# LEDs.net
KiCad netlist of a schematic drawn in Altium Designer
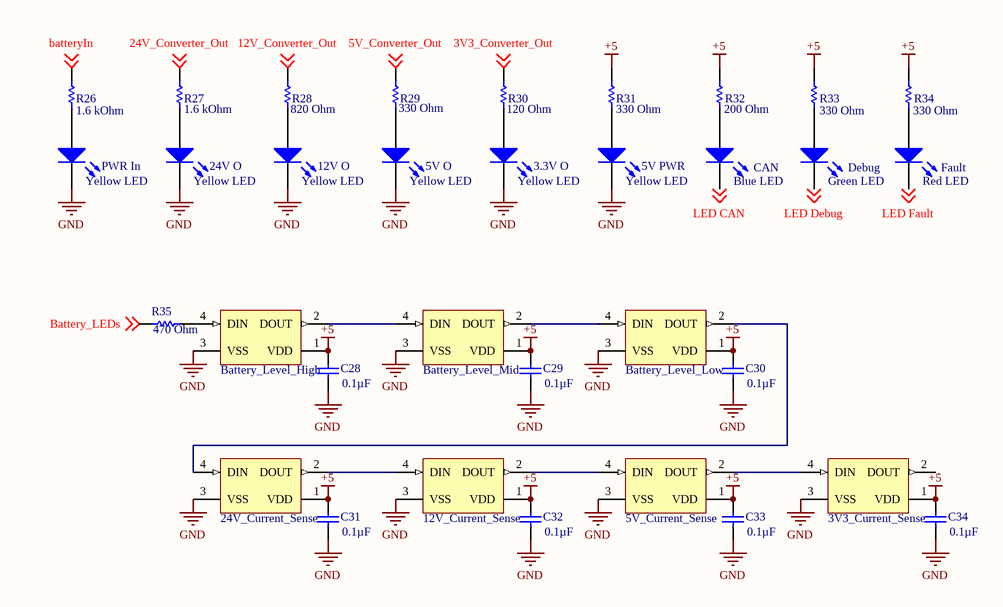
[diagram p0: LEDs.SchDoc]

(export (version "E")
  (design (tool "Eeschema 10.0.6"))
  (components
    (comp (ref "3.3V O")
      (value "Yellow LED")
      (footprint "0805_A")
      (description "Standard 0805 LED")
      (libsource (lib "Husky Robotics Standard Library 2019-2020") (part "LED"))
    )
    (comp (ref "3V3_Current_Sense")
      (value "RBG_LED")
      (footprint "RGB_LED_1")
      (description "LED ADAI-WS2812B-4")
      (fields (field (name "DIGI-KEY_PART_NUMBER") "516-3280-1-ND"))
      (libsource (lib "University of Washington - Husky Robotics Team") (part "RBG_LED"))
    )
    (comp (ref "5V O")
      (value "Yellow LED")
      (footprint "0805_A")
      (description "Standard 0805 LED")
      (libsource (lib "Husky Robotics Standard Library 2019-2020") (part "LED"))
    )
    (comp (ref "5V PWR")
      (value "Yellow LED")
      (footprint "0805_A")
      (description "Standard 0805 LED")
      (libsource (lib "Husky Robotics Standard Library 2019-2020") (part "LED"))
    )
    (comp (ref "5V_Current_Sense")
      (value "RBG_LED")
      (footprint "RGB_LED_1")
      (description "LED ADAI-WS2812B-4")
      (fields (field (name "DIGI-KEY_PART_NUMBER") "516-3280-1-ND"))
      (libsource (lib "University of Washington - Husky Robotics Team") (part "RBG_LED"))
    )
    (comp (ref "12V O")
      (value "Yellow LED")
      (footprint "0805_A")
      (description "Standard 0805 LED")
      (libsource (lib "Husky Robotics Standard Library 2019-2020") (part "LED"))
    )
    (comp (ref "12V_Current_Sense")
      (value "RBG_LED")
      (footprint "RGB_LED_1")
      (description "LED ADAI-WS2812B-4")
      (fields (field (name "DIGI-KEY_PART_NUMBER") "516-3280-1-ND"))
      (libsource (lib "University of Washington - Husky Robotics Team") (part "RBG_LED"))
    )
    (comp (ref "24V O")
      (value "Yellow LED")
      (footprint "0805_A")
      (description "Standard 0805 LED")
      (libsource (lib "Husky Robotics Standard Library 2019-2020") (part "LED"))
    )
    (comp (ref "24V_Current_Sense")
      (value "RBG_LED")
      (footprint "RGB_LED_1")
      (description "LED ADAI-WS2812B-4")
      (fields (field (name "DIGI-KEY_PART_NUMBER") "516-3280-1-ND"))
      (libsource (lib "University of Washington - Husky Robotics Team") (part "RBG_LED"))
    )
    (comp (ref "Battery_Level_High")
      (value "RBG_LED")
      (footprint "RGB_LED_1")
      (description "LED ADAI-WS2812B-4")
      (fields (field (name "DIGI-KEY_PART_NUMBER") "516-3280-1-ND"))
      (libsource (lib "University of Washington - Husky Robotics Team") (part "RBG_LED"))
    )
    (comp (ref "Battery_Level_Low")
      (value "RBG_LED")
      (footprint "RGB_LED_1")
      (description "LED ADAI-WS2812B-4")
      (fields (field (name "DIGI-KEY_PART_NUMBER") "516-3280-1-ND"))
      (libsource (lib "University of Washington - Husky Robotics Team") (part "RBG_LED"))
    )
    (comp (ref "Battery_Level_Mid")
      (value "RBG_LED")
      (footprint "RGB_LED_1")
      (description "LED ADAI-WS2812B-4")
      (fields (field (name "DIGI-KEY_PART_NUMBER") "516-3280-1-ND"))
      (libsource (lib "University of Washington - Husky Robotics Team") (part "RBG_LED"))
    )
    (comp (ref "C28")
      (value "0.1µF")
      (footprint "Cap 0805")
      (description "Standard Capacitor")
      (fields (field (name "DIGI-KEY_PART_NUMBER") "399-1177-1-ND") (field (name "Comment") "0805 Capacitor"))
      (libsource (lib "University of Washington - Husky Robotics Team") (part "0805 Capacitor"))
    )
    (comp (ref "C29")
      (value "0.1µF")
      (footprint "Cap 0805")
      (description "Standard Capacitor")
      (fields (field (name "DIGI-KEY_PART_NUMBER") "399-1177-1-ND") (field (name "Comment") "0805 Capacitor"))
      (libsource (lib "University of Washington - Husky Robotics Team") (part "0805 Capacitor"))
    )
    (comp (ref "C30")
      (value "0.1µF")
      (footprint "Cap 0805")
      (description "Standard Capacitor")
      (fields (field (name "DIGI-KEY_PART_NUMBER") "399-1177-1-ND") (field (name "Comment") "0805 Capacitor"))
      (libsource (lib "University of Washington - Husky Robotics Team") (part "0805 Capacitor"))
    )
    (comp (ref "C31")
      (value "0.1µF")
      (footprint "Cap 0805")
      (description "Standard Capacitor")
      (fields (field (name "DIGI-KEY_PART_NUMBER") "399-1177-1-ND") (field (name "Comment") "0805 Capacitor"))
      (libsource (lib "University of Washington - Husky Robotics Team") (part "0805 Capacitor"))
    )
    (comp (ref "C32")
      (value "0.1µF")
      (footprint "Cap 0805")
      (description "Standard Capacitor")
      (fields (field (name "DIGI-KEY_PART_NUMBER") "399-1177-1-ND") (field (name "Comment") "0805 Capacitor"))
      (libsource (lib "University of Washington - Husky Robotics Team") (part "0805 Capacitor"))
    )
    (comp (ref "C33")
      (value "0.1µF")
      (footprint "Cap 0805")
      (description "Standard Capacitor")
      (fields (field (name "DIGI-KEY_PART_NUMBER") "399-1177-1-ND") (field (name "Comment") "0805 Capacitor"))
      (libsource (lib "University of Washington - Husky Robotics Team") (part "0805 Capacitor"))
    )
    (comp (ref "C34")
      (value "0.1µF")
      (footprint "Cap 0805")
      (description "Standard Capacitor")
      (fields (field (name "DIGI-KEY_PART_NUMBER") "399-1177-1-ND") (field (name "Comment") "0805 Capacitor"))
      (libsource (lib "University of Washington - Husky Robotics Team") (part "0805 Capacitor"))
    )
    (comp (ref "CAN")
      (value "Blue LED")
      (footprint "0805_A")
      (description "Standard 0805 LED")
      (libsource (lib "Husky Robotics Standard Library 2019-2020") (part "LED"))
    )
    (comp (ref "Debug")
      (value "Green LED")
      (footprint "0805_A")
      (description "Standard 0805 LED")
      (libsource (lib "Husky Robotics Standard Library 2019-2020") (part "LED"))
    )
    (comp (ref "Fault")
      (value "Red LED")
      (footprint "0805_A")
      (description "Standard 0805 LED")
      (fields (field (name "MANUFACTURER") "Wuerth Elektronik") (field (name "PARTNUMBER") "150080SS75000"))
      (libsource (lib "Husky Robotics Standard Library 2019-2020") (part "LED"))
    )
    (comp (ref "PWR In")
      (value "Yellow LED")
      (footprint "0805_A")
      (description "Standard 0805 LED")
      (libsource (lib "Husky Robotics Standard Library 2019-2020") (part "LED"))
    )
    (comp (ref "R26")
      (value "1.6 kOhm")
      (footprint "RESC0805(2012)_N")
      (description "Generic 0805 Resistor")
      (fields (field (name "Comment") "Resistor 0805"))
      (libsource (lib "Husky Robotics Standard Library 2019-2020") (part "Resistor 0805"))
    )
    (comp (ref "R27")
      (value "1.6 kOhm")
      (footprint "RESC0805(2012)_N")
      (description "Generic 0805 Resistor")
      (fields (field (name "Comment") "Resistor 0805"))
      (libsource (lib "Husky Robotics Standard Library 2019-2020") (part "Resistor 0805"))
    )
    (comp (ref "R28")
      (value "820 Ohm")
      (footprint "RESC0805(2012)_N")
      (description "Generic 0805 Resistor")
      (fields (field (name "TOLERANCE") "5 %") (field (name "POWER") "0.125 W"))
      (libsource (lib "Husky Robotics Standard Library 2019-2020") (part "Resistor 0805"))
    )
    (comp (ref "R29")
      (value "330 Ohm")
      (footprint "RESC0805(2012)_N")
      (description "Generic 0805 Resistor")
      (fields (field (name "Comment") "Resistor 0805"))
      (libsource (lib "Husky Robotics Standard Library 2019-2020") (part "Resistor 0805"))
    )
    (comp (ref "R30")
      (value "120 Ohm")
      (footprint "RESC0805(2012)_N")
      (description "Generic 0805 Resistor")
      (fields (field (name "TOLERANCE") "5 %") (field (name "POWER") "0.125 W"))
      (libsource (lib "Husky Robotics Standard Library 2019-2020") (part "Resistor 0805"))
    )
    (comp (ref "R31")
      (value "330 Ohm")
      (footprint "RESC0805(2012)_N")
      (description "Generic 0805 Resistor")
      (fields (field (name "Comment") "Resistor 0805"))
      (libsource (lib "Husky Robotics Standard Library 2019-2020") (part "Resistor 0805"))
    )
    (comp (ref "R32")
      (value "200 Ohm")
      (footprint "RESC0805(2012)_N")
      (description "Generic 0805 Resistor")
      (fields (field (name "Comment") "Resistor 0805"))
      (libsource (lib "Husky Robotics Standard Library 2019-2020") (part "Resistor 0805"))
    )
    (comp (ref "R33")
      (value "330 Ohm")
      (footprint "RESC0805(2012)_N")
      (description "Generic 0805 Resistor")
      (fields (field (name "Comment") "Resistor 0805"))
      (libsource (lib "Husky Robotics Standard Library 2019-2020") (part "Resistor 0805"))
    )
    (comp (ref "R34")
      (value "330 Ohm")
      (footprint "RESC0805(2012)_N")
      (description "Generic 0805 Resistor")
      (fields (field (name "Comment") "Resistor 0805"))
      (libsource (lib "Husky Robotics Standard Library 2019-2020") (part "Resistor 0805"))
    )
    (comp (ref "R35")
      (value "470 Ohm")
      (footprint "RESC0805(2012)_N")
      (description "Generic 0805 Resistor")
      (fields (field (name "Comment") "Resistor 0805"))
      (libsource (lib "University of Washington - Husky Robotics Team") (part "Resistor 0805"))
    )
  )
  (nets
    (net (code "1") (name "+5") (class "Default")
      (node (ref "12V_Current_Sense") (pin "1") (pinfunction "VDD_1") (pintype "power_in"))
      (node (ref "24V_Current_Sense") (pin "1") (pinfunction "VDD_1") (pintype "power_in"))
      (node (ref "3V3_Current_Sense") (pin "1") (pinfunction "VDD_1") (pintype "power_in"))
      (node (ref "5V_Current_Sense") (pin "1") (pinfunction "VDD_1") (pintype "power_in"))
      (node (ref "Battery_Level_High") (pin "1") (pinfunction "VDD_1") (pintype "power_in"))
      (node (ref "Battery_Level_Low") (pin "1") (pinfunction "VDD_1") (pintype "power_in"))
      (node (ref "Battery_Level_Mid") (pin "1") (pinfunction "VDD_1") (pintype "power_in"))
      (node (ref "C28") (pin "1") (pinfunction "1_1") (pintype "passive"))
      (node (ref "C29") (pin "1") (pinfunction "1_1") (pintype "passive"))
      (node (ref "C30") (pin "1") (pinfunction "1_1") (pintype "passive"))
      (node (ref "C31") (pin "1") (pinfunction "1_1") (pintype "passive"))
      (node (ref "C32") (pin "1") (pinfunction "1_1") (pintype "passive"))
      (node (ref "C33") (pin "1") (pinfunction "1_1") (pintype "passive"))
      (node (ref "C34") (pin "1") (pinfunction "1_1") (pintype "passive"))
      (node (ref "R31") (pin "1") (pinfunction "1_1") (pintype "passive"))
      (node (ref "R32") (pin "2") (pinfunction "2_2") (pintype "passive"))
      (node (ref "R33") (pin "2") (pinfunction "2_2") (pintype "passive"))
      (node (ref "R34") (pin "2") (pinfunction "2_2") (pintype "passive"))
    )
    (net (code "2") (name "3V3_Converter_Out") (class "Default")
      (node (ref "R30") (pin "1") (pinfunction "1_1") (pintype "passive"))
    )
    (net (code "3") (name "5V_Converter_Out") (class "Default")
      (node (ref "R29") (pin "1") (pinfunction "1_1") (pintype "passive"))
    )
    (net (code "4") (name "12V_Converter_Out") (class "Default")
      (node (ref "R28") (pin "2") (pinfunction "2_2") (pintype "passive"))
    )
    (net (code "5") (name "24V_Converter_Out") (class "Default")
      (node (ref "R27") (pin "1") (pinfunction "1_1") (pintype "passive"))
    )
    (net (code "6") (name "Battery_LEDs") (class "Default")
      (node (ref "R35") (pin "1") (pinfunction "1_1") (pintype "passive"))
    )
    (net (code "7") (name "GND") (class "Default")
      (node (ref "12V O") (pin "1") (pinfunction "K_1") (pintype "passive"))
      (node (ref "12V_Current_Sense") (pin "3") (pinfunction "VSS_3") (pintype "power_in"))
      (node (ref "24V O") (pin "1") (pinfunction "K_1") (pintype "passive"))
      (node (ref "24V_Current_Sense") (pin "3") (pinfunction "VSS_3") (pintype "power_in"))
      (node (ref "3.3V O") (pin "1") (pinfunction "K_1") (pintype "passive"))
      (node (ref "3V3_Current_Sense") (pin "3") (pinfunction "VSS_3") (pintype "power_in"))
      (node (ref "5V O") (pin "1") (pinfunction "K_1") (pintype "passive"))
      (node (ref "5V PWR") (pin "1") (pinfunction "K_1") (pintype "passive"))
      (node (ref "5V_Current_Sense") (pin "3") (pinfunction "VSS_3") (pintype "power_in"))
      (node (ref "Battery_Level_High") (pin "3") (pinfunction "VSS_3") (pintype "power_in"))
      (node (ref "Battery_Level_Low") (pin "3") (pinfunction "VSS_3") (pintype "power_in"))
      (node (ref "Battery_Level_Mid") (pin "3") (pinfunction "VSS_3") (pintype "power_in"))
      (node (ref "C28") (pin "2") (pinfunction "2_2") (pintype "passive"))
      (node (ref "C29") (pin "2") (pinfunction "2_2") (pintype "passive"))
      (node (ref "C30") (pin "2") (pinfunction "2_2") (pintype "passive"))
      (node (ref "C31") (pin "2") (pinfunction "2_2") (pintype "passive"))
      (node (ref "C32") (pin "2") (pinfunction "2_2") (pintype "passive"))
      (node (ref "C33") (pin "2") (pinfunction "2_2") (pintype "passive"))
      (node (ref "C34") (pin "2") (pinfunction "2_2") (pintype "passive"))
      (node (ref "PWR In") (pin "1") (pinfunction "K_1") (pintype "passive"))
    )
    (net (code "8") (name "LED CAN") (class "Default")
      (node (ref "CAN") (pin "1") (pinfunction "K_1") (pintype "passive"))
    )
    (net (code "9") (name "LED Debug") (class "Default")
      (node (ref "Debug") (pin "1") (pinfunction "K_1") (pintype "passive"))
    )
    (net (code "10") (name "LED Fault") (class "Default")
      (node (ref "Fault") (pin "1") (pinfunction "K_1") (pintype "passive"))
    )
    (net (code "11") (name "Net-(3.3V O-A)") (class "Default")
      (node (ref "3.3V O") (pin "2") (pinfunction "A_2") (pintype "passive"))
      (node (ref "R30") (pin "2") (pinfunction "2_2") (pintype "passive"))
    )
    (net (code "12") (name "Net-(3V3_Current_Sense-DIN)") (class "Default")
      (node (ref "3V3_Current_Sense") (pin "4") (pinfunction "DIN_4") (pintype "input"))
      (node (ref "5V_Current_Sense") (pin "2") (pinfunction "DOUT_2") (pintype "output"))
    )
    (net (code "13") (name "Net-(5V O-A)") (class "Default")
      (node (ref "5V O") (pin "2") (pinfunction "A_2") (pintype "passive"))
      (node (ref "R29") (pin "2") (pinfunction "2_2") (pintype "passive"))
    )
    (net (code "14") (name "Net-(5V PWR-A)") (class "Default")
      (node (ref "5V PWR") (pin "2") (pinfunction "A_2") (pintype "passive"))
      (node (ref "R31") (pin "2") (pinfunction "2_2") (pintype "passive"))
    )
    (net (code "15") (name "Net-(12V O-A)") (class "Default")
      (node (ref "12V O") (pin "2") (pinfunction "A_2") (pintype "passive"))
      (node (ref "R28") (pin "1") (pinfunction "1_1") (pintype "passive"))
    )
    (net (code "16") (name "Net-(12V_Current_Sense-DIN)") (class "Default")
      (node (ref "12V_Current_Sense") (pin "4") (pinfunction "DIN_4") (pintype "input"))
      (node (ref "24V_Current_Sense") (pin "2") (pinfunction "DOUT_2") (pintype "output"))
    )
    (net (code "17") (name "Net-(12V_Current_Sense-DOUT)") (class "Default")
      (node (ref "12V_Current_Sense") (pin "2") (pinfunction "DOUT_2") (pintype "output"))
      (node (ref "5V_Current_Sense") (pin "4") (pinfunction "DIN_4") (pintype "input"))
    )
    (net (code "18") (name "Net-(24V O-A)") (class "Default")
      (node (ref "24V O") (pin "2") (pinfunction "A_2") (pintype "passive"))
      (node (ref "R27") (pin "2") (pinfunction "2_2") (pintype "passive"))
    )
    (net (code "19") (name "Net-(24V_Current_Sense-DIN)") (class "Default")
      (node (ref "24V_Current_Sense") (pin "4") (pinfunction "DIN_4") (pintype "input"))
      (node (ref "Battery_Level_Low") (pin "2") (pinfunction "DOUT_2") (pintype "output"))
    )
    (net (code "20") (name "Net-(Battery_Level_High-DIN)") (class "Default")
      (node (ref "Battery_Level_High") (pin "4") (pinfunction "DIN_4") (pintype "input"))
      (node (ref "R35") (pin "2") (pinfunction "2_2") (pintype "passive"))
    )
    (net (code "21") (name "Net-(Battery_Level_High-DOUT)") (class "Default")
      (node (ref "Battery_Level_High") (pin "2") (pinfunction "DOUT_2") (pintype "output"))
      (node (ref "Battery_Level_Mid") (pin "4") (pinfunction "DIN_4") (pintype "input"))
    )
    (net (code "22") (name "Net-(Battery_Level_Low-DIN)") (class "Default")
      (node (ref "Battery_Level_Low") (pin "4") (pinfunction "DIN_4") (pintype "input"))
      (node (ref "Battery_Level_Mid") (pin "2") (pinfunction "DOUT_2") (pintype "output"))
    )
    (net (code "23") (name "Net-(CAN-A)") (class "Default")
      (node (ref "CAN") (pin "2") (pinfunction "A_2") (pintype "passive"))
      (node (ref "R32") (pin "1") (pinfunction "1_1") (pintype "passive"))
    )
    (net (code "24") (name "Net-(Debug-A)") (class "Default")
      (node (ref "Debug") (pin "2") (pinfunction "A_2") (pintype "passive"))
      (node (ref "R33") (pin "1") (pinfunction "1_1") (pintype "passive"))
    )
    (net (code "25") (name "Net-(Fault-A)") (class "Default")
      (node (ref "Fault") (pin "2") (pinfunction "A_2") (pintype "passive"))
      (node (ref "R34") (pin "1") (pinfunction "1_1") (pintype "passive"))
    )
    (net (code "26") (name "Net-(PWR In-A)") (class "Default")
      (node (ref "PWR In") (pin "2") (pinfunction "A_2") (pintype "passive"))
      (node (ref "R26") (pin "1") (pinfunction "1_1") (pintype "passive"))
    )
    (net (code "27") (name "batteryIn") (class "Default")
      (node (ref "R26") (pin "2") (pinfunction "2_2") (pintype "passive"))
    )
    (net (code "28") (name "unconnected-(3V3_Current_Sense-DOUT-Pad2)") (class "Default")
      (node (ref "3V3_Current_Sense") (pin "2") (pinfunction "DOUT_2") (pintype "output"))
    )
  )
)
